# threshold_control_device.net
KiCad netlist of a schematic drawn in EAGLE
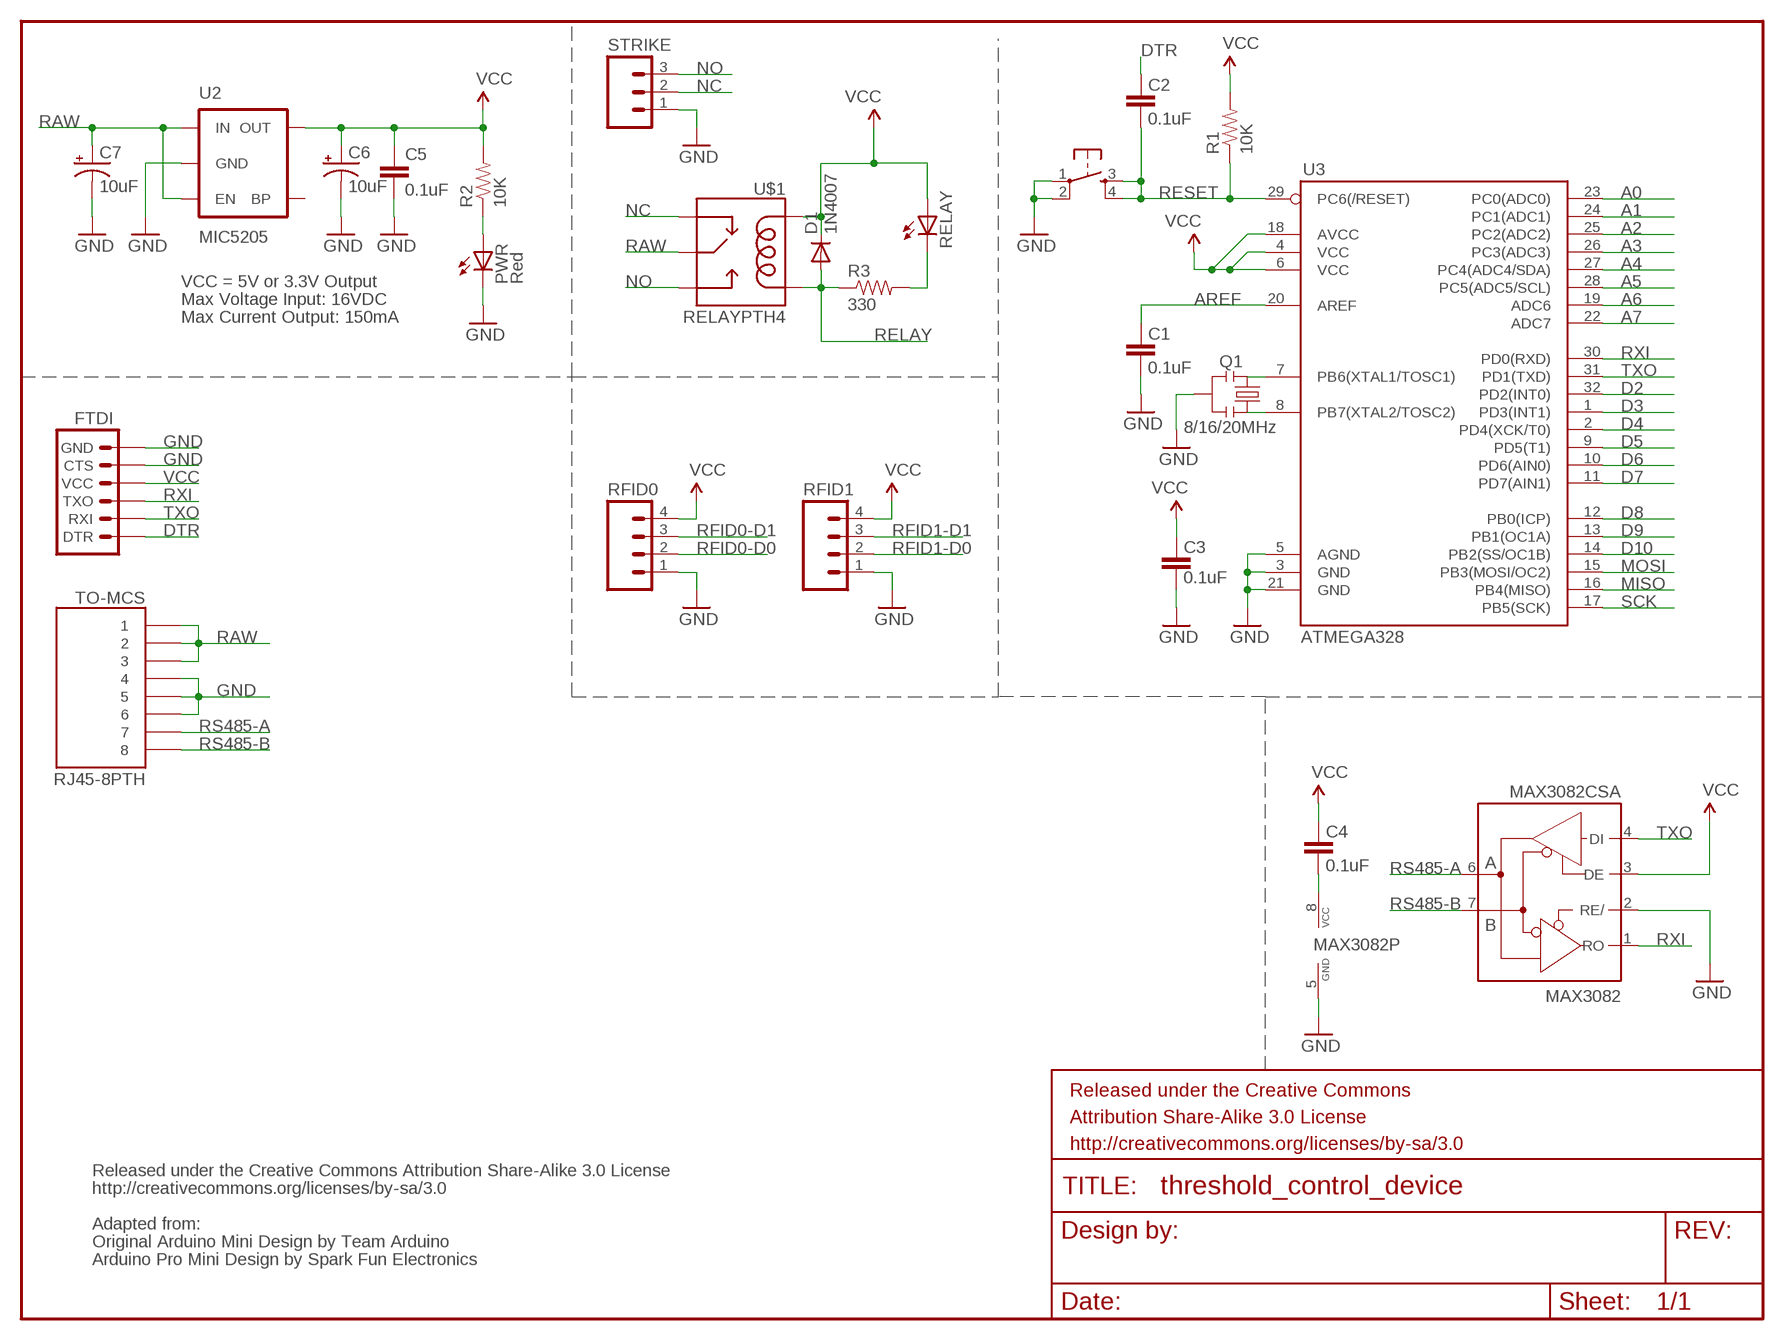
[diagram p0: schematic, sheet 1]

(export (version "E")
  (design (tool "Eeschema 10.0.6"))
  (components
    (comp (ref "C1")
      (value "0.1uF")
      (footprint "eagle-import:0402-CAP")
      (libsource (lib "eagle-import") (part "CAP0402-CAP"))
    )
    (comp (ref "C2")
      (value "0.1uF")
      (footprint "eagle-import:0402-CAP")
      (libsource (lib "eagle-import") (part "CAP0402-CAP"))
    )
    (comp (ref "C3")
      (value "0.1uF")
      (footprint "eagle-import:0402-CAP")
      (libsource (lib "eagle-import") (part "CAP0402-CAP"))
    )
    (comp (ref "C4")
      (value "0.1uF")
      (footprint "eagle-import:0402-CAP")
      (libsource (lib "eagle-import") (part "CAP0402-CAP"))
    )
    (comp (ref "C5")
      (value "0.1uF")
      (footprint "eagle-import:0402-CAP")
      (libsource (lib "eagle-import") (part "CAP0402-CAP"))
    )
    (comp (ref "C6")
      (value "10uF")
      (footprint "eagle-import:EIA3216")
      (libsource (lib "eagle-import") (part "CAP_POL1206"))
    )
    (comp (ref "C7")
      (value "10uF")
      (footprint "eagle-import:EIA3216")
      (libsource (lib "eagle-import") (part "CAP_POL1206"))
    )
    (comp (ref "D1")
      (value "1N4007")
      (footprint "eagle-import:DIODE-1N4001")
      (libsource (lib "eagle-import") (part "DIODEPTH"))
    )
    (comp (ref "FRAME1")
      (value "FRAME-LETTER")
      (footprint "eagle-import:CREATIVE_COMMONS")
      (libsource (lib "eagle-import") (part "FRAME-LETTER"))
    )
    (comp (ref "FTDI")
      (value "ARDUINO_SERIAL_PROGRAMSMD")
      (footprint "eagle-import:1X06-SMD")
      (libsource (lib "eagle-import") (part "ARDUINO_SERIAL_PROGRAMSMD"))
    )
    (comp (ref "MAX3082")
      (value "MAX3082CSA")
      (footprint "eagle-import:SO08")
      (fields (field (name "MF") "MAXIM") (field (name "MPN") "MAX481CSA"))
      (libsource (lib "eagle-import") (part "MAX481CSA"))
    )
    (comp (ref "PWR")
      (value "Red")
      (footprint "eagle-import:LED-0603")
      (libsource (lib "eagle-import") (part "LED0603"))
    )
    (comp (ref "Q1")
      (value "8/16/20MHz")
      (footprint "eagle-import:RESONATOR-SMD")
      (libsource (lib "eagle-import") (part "RESONATORSMD"))
    )
    (comp (ref "R1")
      (value "10K")
      (footprint "eagle-import:0402-RES")
      (libsource (lib "eagle-import") (part "RESISTOR0402-RES"))
    )
    (comp (ref "R2")
      (value "10K")
      (footprint "eagle-import:0402-RES")
      (libsource (lib "eagle-import") (part "RESISTOR0402-RES"))
    )
    (comp (ref "R3")
      (value "330")
      (footprint "eagle-import:AXIAL-0.4")
      (libsource (lib "eagle-import") (part "RESISTORPTH-1/4W"))
    )
    (comp (ref "RELAY")
      (value "LED5MM")
      (footprint "eagle-import:LED5MM")
      (libsource (lib "eagle-import") (part "LED5MM"))
    )
    (comp (ref "RESET")
      (value "Reset")
      (footprint "eagle-import:TACTILE_SWITCH_SMD")
      (libsource (lib "eagle-import") (part "TAC_SWITCHSMD"))
    )
    (comp (ref "RFID0")
      (value "M04SCREW")
      (footprint "eagle-import:SCREWTERMINAL-3.5MM-4")
      (libsource (lib "eagle-import") (part "M04SCREW"))
    )
    (comp (ref "RFID1")
      (value "M04SCREW")
      (footprint "eagle-import:SCREWTERMINAL-3.5MM-4")
      (libsource (lib "eagle-import") (part "M04SCREW"))
    )
    (comp (ref "STRIKE")
      (value "M03SCREW")
      (footprint "eagle-import:SCREWTERMINAL-3.5MM-3")
      (libsource (lib "eagle-import") (part "M03SCREW"))
    )
    (comp (ref "TO-MCS")
      (value "RJ45-8PTH")
      (footprint "eagle-import:RJ45-8")
      (libsource (lib "eagle-import") (part "RJ45-8PTH"))
    )
    (comp (ref "U$1")
      (value "RELAYPTH4")
      (footprint "eagle-import:RELAY-JZC")
      (libsource (lib "eagle-import") (part "RELAYPTH4"))
    )
    (comp (ref "U2")
      (value "MIC5205")
      (footprint "eagle-import:SOT23-5")
      (libsource (lib "eagle-import") (part "V_REG_LDOSMD"))
    )
    (comp (ref "U3")
      (value "ATMEGA328")
      (footprint "eagle-import:TQFP32-08")
      (libsource (lib "eagle-import") (part "ATMEGA168"))
    )
  )
  (nets
    (net (code "1") (name "/A0") (class "Default")
      (node (ref "U3") (pin "23") (pinfunction "PC0(ADC0)_23") (pintype "bidirectional"))
    )
    (net (code "2") (name "/A1") (class "Default")
      (node (ref "U3") (pin "24") (pinfunction "PC1(ADC1)_24") (pintype "bidirectional"))
    )
    (net (code "3") (name "/A2") (class "Default")
      (node (ref "U3") (pin "25") (pinfunction "PC2(ADC2)_25") (pintype "bidirectional"))
    )
    (net (code "4") (name "/A3") (class "Default")
      (node (ref "U3") (pin "26") (pinfunction "PC3(ADC3)_26") (pintype "bidirectional"))
    )
    (net (code "5") (name "/A4") (class "Default")
      (node (ref "U3") (pin "27") (pinfunction "PC4(ADC4/SDA)_27") (pintype "bidirectional"))
    )
    (net (code "6") (name "/A5") (class "Default")
      (node (ref "U3") (pin "28") (pinfunction "PC5(ADC5/SCL)_28") (pintype "bidirectional"))
    )
    (net (code "7") (name "/A6") (class "Default")
      (node (ref "U3") (pin "19") (pinfunction "ADC6_19") (pintype "bidirectional"))
    )
    (net (code "8") (name "/A7") (class "Default")
      (node (ref "U3") (pin "22") (pinfunction "ADC7_22") (pintype "bidirectional"))
    )
    (net (code "9") (name "/AREF") (class "Default")
      (node (ref "C1") (pin "2") (pinfunction "2_2") (pintype "passive"))
      (node (ref "U3") (pin "20") (pinfunction "AREF_20") (pintype "bidirectional"))
    )
    (net (code "10") (name "/D2") (class "Default")
      (node (ref "U3") (pin "32") (pinfunction "PD2(INT0)_32") (pintype "bidirectional"))
    )
    (net (code "11") (name "/D3") (class "Default")
      (node (ref "U3") (pin "1") (pinfunction "PD3(INT1)_1") (pintype "bidirectional"))
    )
    (net (code "12") (name "/D4") (class "Default")
      (node (ref "U3") (pin "2") (pinfunction "PD4(XCK/T0)_2") (pintype "bidirectional"))
    )
    (net (code "13") (name "/D5") (class "Default")
      (node (ref "U3") (pin "9") (pinfunction "PD5(T1)_9") (pintype "bidirectional"))
    )
    (net (code "14") (name "/D6") (class "Default")
      (node (ref "U3") (pin "10") (pinfunction "PD6(AIN0)_10") (pintype "bidirectional"))
    )
    (net (code "15") (name "/D7") (class "Default")
      (node (ref "U3") (pin "11") (pinfunction "PD7(AIN1)_11") (pintype "bidirectional"))
    )
    (net (code "16") (name "/D8") (class "Default")
      (node (ref "U3") (pin "12") (pinfunction "PB0(ICP)_12") (pintype "bidirectional"))
    )
    (net (code "17") (name "/D9") (class "Default")
      (node (ref "U3") (pin "13") (pinfunction "PB1(OC1A)_13") (pintype "bidirectional"))
    )
    (net (code "18") (name "/D10") (class "Default")
      (node (ref "U3") (pin "14") (pinfunction "PB2(SS/OC1B)_14") (pintype "bidirectional"))
    )
    (net (code "19") (name "/DTR") (class "Default")
      (node (ref "C2") (pin "2") (pinfunction "2_2") (pintype "passive"))
      (node (ref "FTDI") (pin "1") (pinfunction "DTR_1") (pintype "passive"))
    )
    (net (code "20") (name "/MISO") (class "Default")
      (node (ref "U3") (pin "16") (pinfunction "PB4(MISO)_16") (pintype "bidirectional"))
    )
    (net (code "21") (name "/MOSI") (class "Default")
      (node (ref "U3") (pin "15") (pinfunction "PB3(MOSI/OC2)_15") (pintype "bidirectional"))
    )
    (net (code "22") (name "/NC") (class "Default")
      (node (ref "STRIKE") (pin "2") (pinfunction "2_2") (pintype "passive"))
      (node (ref "U$1") (pin "2") (pinfunction "NC_2") (pintype "bidirectional"))
    )
    (net (code "23") (name "/NO") (class "Default")
      (node (ref "STRIKE") (pin "3") (pinfunction "3_3") (pintype "passive"))
      (node (ref "U$1") (pin "3") (pinfunction "NO_3") (pintype "bidirectional"))
    )
    (net (code "24") (name "/RAW") (class "Default")
      (node (ref "C7") (pin "A") (pinfunction "+_A") (pintype "passive"))
      (node (ref "TO-MCS") (pin "1") (pinfunction "1_1") (pintype "bidirectional"))
      (node (ref "TO-MCS") (pin "2") (pinfunction "2_2") (pintype "bidirectional"))
      (node (ref "TO-MCS") (pin "3") (pinfunction "3_3") (pintype "bidirectional"))
      (node (ref "U$1") (pin "4") (pinfunction "MAIN_4") (pintype "bidirectional"))
      (node (ref "U2") (pin "1") (pinfunction "IN_1") (pintype "input"))
      (node (ref "U2") (pin "3") (pinfunction "EN_3") (pintype "input"))
    )
    (net (code "25") (name "/RELAY") (class "Default")
      (node (ref "D1") (pin "A") (pinfunction "A_A") (pintype "passive"))
      (node (ref "R3") (pin "P$1") (pinfunction "1_P$1") (pintype "passive"))
      (node (ref "U$1") (pin "1") (pinfunction "COIL2_1") (pintype "bidirectional"))
    )
    (net (code "26") (name "/RESET") (class "Default")
      (node (ref "C2") (pin "1") (pinfunction "1_1") (pintype "passive"))
      (node (ref "R1") (pin "1") (pinfunction "1_1") (pintype "passive"))
      (node (ref "RESET") (pin "3") (pinfunction "3_3") (pintype "passive"))
      (node (ref "RESET") (pin "4") (pinfunction "4_4") (pintype "passive"))
      (node (ref "U3") (pin "29") (pinfunction "PC6(/RESET)_29") (pintype "bidirectional"))
    )
    (net (code "27") (name "/RFID0-D0") (class "Default")
      (node (ref "RFID0") (pin "2") (pinfunction "2_2") (pintype "passive"))
    )
    (net (code "28") (name "/RFID0-D1") (class "Default")
      (node (ref "RFID0") (pin "3") (pinfunction "3_3") (pintype "passive"))
    )
    (net (code "29") (name "/RFID1-D0") (class "Default")
      (node (ref "RFID1") (pin "2") (pinfunction "2_2") (pintype "passive"))
    )
    (net (code "30") (name "/RFID1-D1") (class "Default")
      (node (ref "RFID1") (pin "3") (pinfunction "3_3") (pintype "passive"))
    )
    (net (code "31") (name "/RS485-A") (class "Default")
      (node (ref "MAX3082") (pin "6") (pinfunction "A_6") (pintype "passive"))
      (node (ref "TO-MCS") (pin "7") (pinfunction "7_7") (pintype "bidirectional"))
    )
    (net (code "32") (name "/RS485-B") (class "Default")
      (node (ref "MAX3082") (pin "7") (pinfunction "B_7") (pintype "passive"))
      (node (ref "TO-MCS") (pin "8") (pinfunction "8_8") (pintype "bidirectional"))
    )
    (net (code "33") (name "/RXI") (class "Default")
      (node (ref "FTDI") (pin "3") (pinfunction "TXO_3") (pintype "passive"))
      (node (ref "MAX3082") (pin "1") (pinfunction "RO_1") (pintype "output"))
      (node (ref "U3") (pin "30") (pinfunction "PD0(RXD)_30") (pintype "bidirectional"))
    )
    (net (code "34") (name "/SCK") (class "Default")
      (node (ref "U3") (pin "17") (pinfunction "PB5(SCK)_17") (pintype "bidirectional"))
    )
    (net (code "35") (name "/TXO") (class "Default")
      (node (ref "FTDI") (pin "2") (pinfunction "RXI_2") (pintype "passive"))
      (node (ref "MAX3082") (pin "4") (pinfunction "DI_4") (pintype "input"))
      (node (ref "U3") (pin "31") (pinfunction "PD1(TXD)_31") (pintype "bidirectional"))
    )
    (net (code "36") (name "GND") (class "Default")
      (node (ref "C1") (pin "1") (pinfunction "1_1") (pintype "passive"))
      (node (ref "C3") (pin "1") (pinfunction "1_1") (pintype "passive"))
      (node (ref "C5") (pin "2") (pinfunction "2_2") (pintype "passive"))
      (node (ref "C6") (pin "C") (pinfunction "-_C") (pintype "passive"))
      (node (ref "C7") (pin "C") (pinfunction "-_C") (pintype "passive"))
      (node (ref "FTDI") (pin "5") (pinfunction "CTS_5") (pintype "passive"))
      (node (ref "FTDI") (pin "6") (pinfunction "GND_6") (pintype "passive"))
      (node (ref "MAX3082") (pin "2") (pinfunction "RE/_2") (pintype "input"))
      (node (ref "MAX3082") (pin "5") (pinfunction "GND_5") (pintype "power_in"))
      (node (ref "PWR") (pin "C") (pinfunction "C_C") (pintype "passive"))
      (node (ref "Q1") (pin "2") (pinfunction "2_2") (pintype "passive"))
      (node (ref "RESET") (pin "1") (pinfunction "1_1") (pintype "passive"))
      (node (ref "RESET") (pin "2") (pinfunction "2_2") (pintype "passive"))
      (node (ref "RFID0") (pin "1") (pinfunction "1_1") (pintype "passive"))
      (node (ref "RFID1") (pin "1") (pinfunction "1_1") (pintype "passive"))
      (node (ref "STRIKE") (pin "1") (pinfunction "1_1") (pintype "passive"))
      (node (ref "TO-MCS") (pin "4") (pinfunction "4_4") (pintype "bidirectional"))
      (node (ref "TO-MCS") (pin "5") (pinfunction "5_5") (pintype "bidirectional"))
      (node (ref "TO-MCS") (pin "6") (pinfunction "6_6") (pintype "bidirectional"))
      (node (ref "U2") (pin "2") (pinfunction "GND_2") (pintype "input"))
      (node (ref "U3") (pin "21") (pinfunction "GND_21") (pintype "bidirectional"))
      (node (ref "U3") (pin "3") (pinfunction "GND_3") (pintype "bidirectional"))
      (node (ref "U3") (pin "5") (pinfunction "AGND_5") (pintype "bidirectional"))
    )
    (net (code "37") (name "Net-(MAX3082B-VCC)") (class "Default")
      (node (ref "C4") (pin "1") (pinfunction "1_1") (pintype "passive"))
      (node (ref "MAX3082") (pin "8") (pinfunction "VCC_8") (pintype "power_in"))
    )
    (net (code "38") (name "Net-(PWR-PadA)") (class "Default")
      (node (ref "PWR") (pin "A") (pinfunction "A_A") (pintype "passive"))
      (node (ref "R2") (pin "1") (pinfunction "1_1") (pintype "passive"))
    )
    (net (code "39") (name "Net-(R3-2)") (class "Default")
      (node (ref "R3") (pin "P$2") (pinfunction "2_P$2") (pintype "passive"))
      (node (ref "RELAY") (pin "K") (pinfunction "C_K") (pintype "passive"))
    )
    (net (code "40") (name "Net-(U3-PB6(XTAL1{slash}TOSC1))") (class "Default")
      (node (ref "Q1") (pin "3") (pinfunction "3_3") (pintype "passive"))
      (node (ref "U3") (pin "7") (pinfunction "PB6(XTAL1/TOSC1)_7") (pintype "bidirectional"))
    )
    (net (code "41") (name "Net-(U3-PB7(XTAL2{slash}TOSC2))") (class "Default")
      (node (ref "Q1") (pin "1") (pinfunction "1_1") (pintype "passive"))
      (node (ref "U3") (pin "8") (pinfunction "PB7(XTAL2/TOSC2)_8") (pintype "bidirectional"))
    )
    (net (code "42") (name "VCC") (class "Default")
      (node (ref "C3") (pin "2") (pinfunction "2_2") (pintype "passive"))
      (node (ref "C4") (pin "2") (pinfunction "2_2") (pintype "passive"))
      (node (ref "C5") (pin "1") (pinfunction "1_1") (pintype "passive"))
      (node (ref "C6") (pin "A") (pinfunction "+_A") (pintype "passive"))
      (node (ref "D1") (pin "C") (pinfunction "C_C") (pintype "passive"))
      (node (ref "FTDI") (pin "4") (pinfunction "VCC_4") (pintype "passive"))
      (node (ref "MAX3082") (pin "3") (pinfunction "DE_3") (pintype "input"))
      (node (ref "R1") (pin "2") (pinfunction "2_2") (pintype "passive"))
      (node (ref "R2") (pin "2") (pinfunction "2_2") (pintype "passive"))
      (node (ref "RELAY") (pin "A") (pinfunction "A_A") (pintype "passive"))
      (node (ref "RFID0") (pin "4") (pinfunction "4_4") (pintype "passive"))
      (node (ref "RFID1") (pin "4") (pinfunction "4_4") (pintype "passive"))
      (node (ref "U$1") (pin "5") (pinfunction "COIL1_5") (pintype "bidirectional"))
      (node (ref "U2") (pin "5") (pinfunction "OUT_5") (pintype "passive"))
      (node (ref "U3") (pin "18") (pinfunction "AVCC_18") (pintype "bidirectional"))
      (node (ref "U3") (pin "4") (pinfunction "VCC_4") (pintype "bidirectional"))
      (node (ref "U3") (pin "6") (pinfunction "VCC_6") (pintype "bidirectional"))
    )
    (net (code "43") (name "unconnected-(U2-BP-Pad4)") (class "Default")
      (node (ref "U2") (pin "4") (pinfunction "BP_4") (pintype "input"))
    )
  )
)
